# AC_DC_Powersupply.net
KiCad netlist of a schematic drawn in Altium Designer
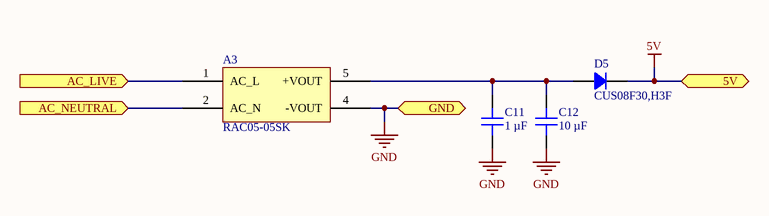
[diagram p0: AC DC Powersupply.SchDoc]

(export (version "E")
  (design (tool "Eeschema 10.0.6"))
  (components
    (comp (ref "A3")
      (value "RAC05-05SK")
      (footprint "RECOM RAC05-K")
      (description "AC/DC CONVERTER 5V 5W")
      (fields (field (name "MANUFACTURER") "Recom Power"))
      (libsource (lib "altiumlibrary.com") (part "RECOM RAC05-K"))
    )
    (comp (ref "C11")
      (value "1 µF")
      (footprint "CAP 0805_2012")
      (description "CAP CER 1UF 50V X7R 0805")
      (fields
        (field (name "PART NUMBER") "GCJ21BR71H105KA01L")
        (field (name "MANUFACTURER") "Murata Electronics")
      )
      (libsource (lib "altiumlibrary.com") (part "Capacitor"))
    )
    (comp (ref "C12")
      (value "10 µF")
      (footprint "CAP 0805_2012")
      (description "CAP CER 10UF 16V X5R 0805")
      (fields
        (field (name "PART NUMBER") "CL21A106KOQNNNE")
        (field (name "MANUFACTURER") "Samsung Electro-Mechanics")
      )
      (libsource (lib "altiumlibrary.com") (part "Capacitor"))
    )
    (comp (ref "D5")
      (value "CUS08F30,H3F")
      (footprint "SOD323")
      (description "DIODE SCHOTTKY 30V 800MA USC")
      (fields (field (name "MANUFACTURER") "Toshiba Semiconductor and Storage"))
      (libsource (lib "altiumlibrary.com") (part "Diode"))
    )
  )
  (nets
    (net (code "1") (name "/AC_LIVE") (class "Default")
      (node (ref "A3") (pin "1") (pinfunction "AC_L_1") (pintype "passive"))
    )
    (net (code "2") (name "/AC_NEUTRAL") (class "Default")
      (node (ref "A3") (pin "2") (pinfunction "AC_N_2") (pintype "passive"))
    )
    (net (code "3") (name "5V") (class "Default")
      (node (ref "D5") (pin "2") (pinfunction "2_2") (pintype "passive"))
    )
    (net (code "4") (name "GND") (class "Default")
      (node (ref "A3") (pin "4") (pinfunction "-VOUT_4") (pintype "passive"))
      (node (ref "C11") (pin "1") (pinfunction "1_1") (pintype "passive"))
      (node (ref "C12") (pin "1") (pinfunction "1_1") (pintype "passive"))
    )
    (net (code "5") (name "Net-(A3-+VOUT)") (class "Default")
      (node (ref "A3") (pin "5") (pinfunction "+VOUT_5") (pintype "passive"))
      (node (ref "C11") (pin "2") (pinfunction "2_2") (pintype "passive"))
      (node (ref "C12") (pin "2") (pinfunction "2_2") (pintype "passive"))
      (node (ref "D5") (pin "1") (pinfunction "1_1") (pintype "passive"))
    )
  )
)
